# Sheet_1.net
KiCad netlist of a schematic drawn in EasyEDA
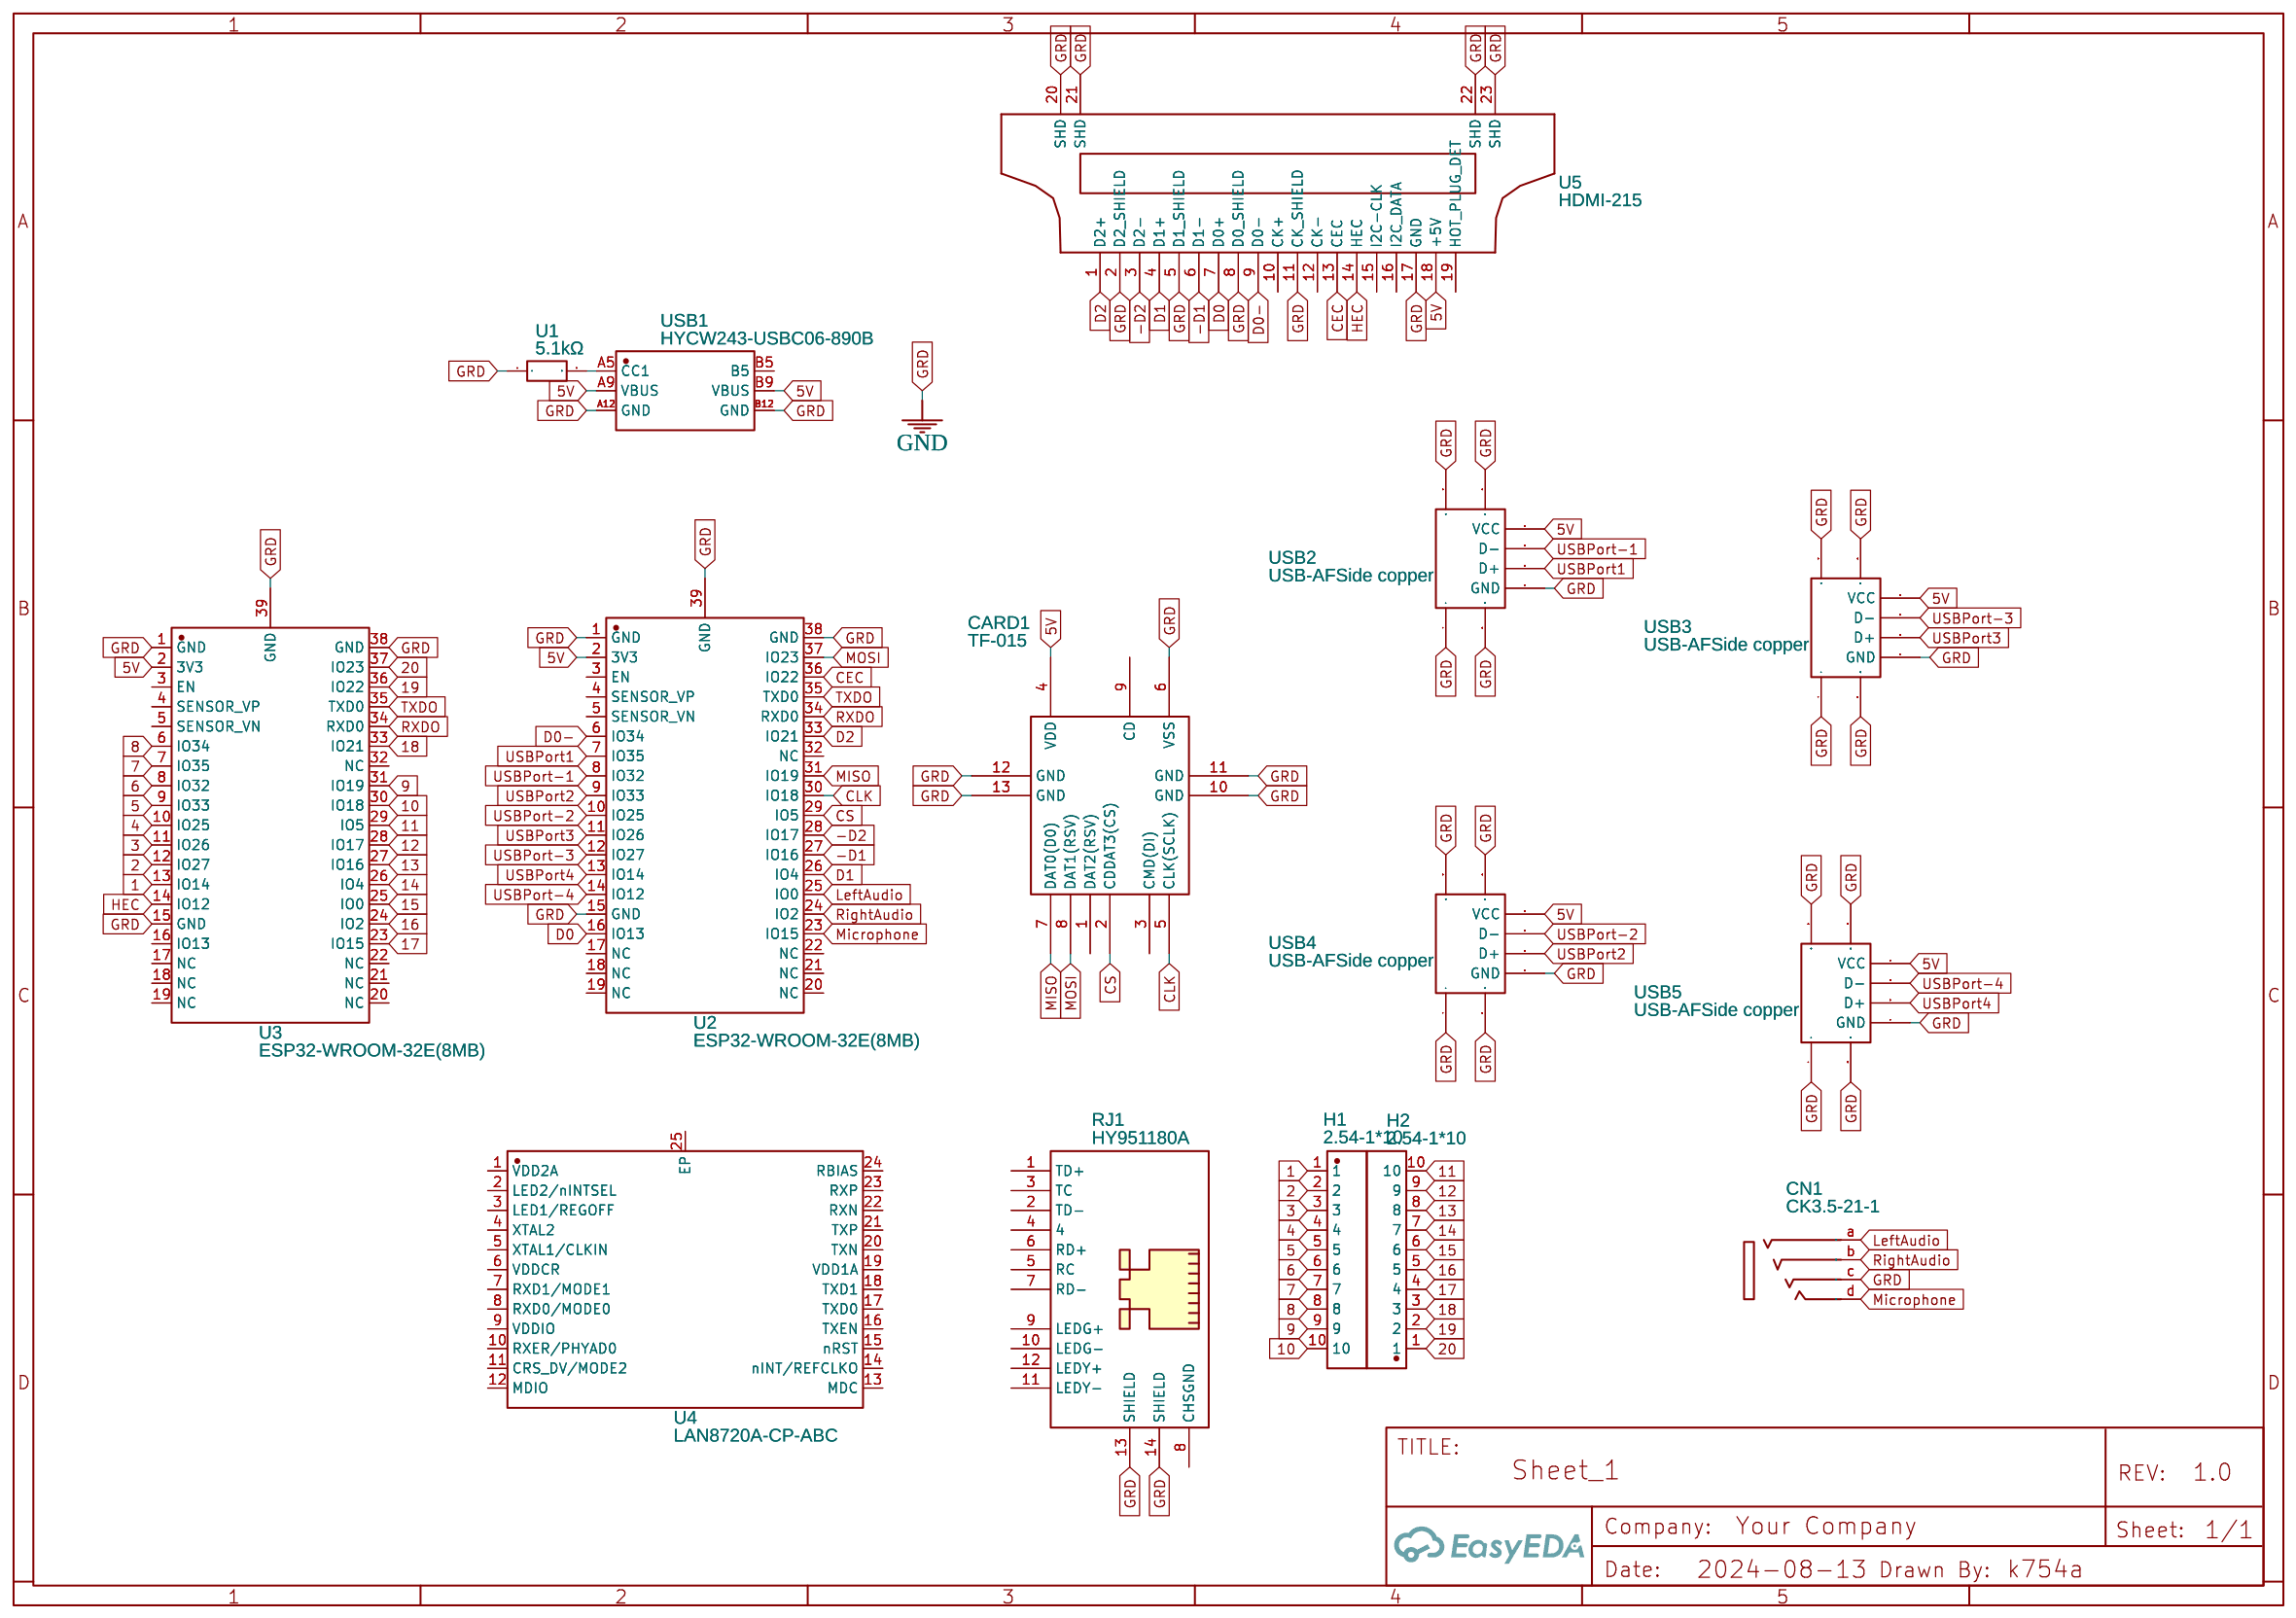
[diagram p0: schematic sheet]

(export (version "E")
  (design (tool "Eeschema 10.0.6"))
  (components
    (comp (ref "CARD1")
      (value "TF-015")
      (fields (field (name "Manufacturer") "SOFNG(硕方)"))
      (libsource (lib "") (part "TF-015"))
    )
    (comp (ref "CN1")
      (value "CK3.5-21-1")
      (fields (field (name "Manufacturer") "JINJIA(金佳)"))
      (libsource (lib "") (part "CK3.5-21-1"))
    )
    (comp (ref "H1")
      (value "2.54-1*10")
      (fields (field (name "Manufacturer") "ZHOURI(洲日)"))
      (libsource (lib "") (part "2.54-1*10_1"))
    )
    (comp (ref "H2")
      (value "2.54-1*10")
      (fields (field (name "Manufacturer") "ZHOURI(洲日)"))
      (libsource (lib "") (part "2.54-1*10"))
    )
    (comp (ref "RJ1")
      (value "HY951180A")
      (fields (field (name "Manufacturer") "HANRUN(汉仁)"))
      (libsource (lib "") (part "HY951180A"))
    )
    (comp (ref "U1")
      (value "5.1kΩ")
      (fields (field (name "Manufacturer Part") "CR1/8W-5K1±5%-ST52") (field (name "Manufacturer") "VO(翔胜)"))
      (libsource (lib "") (part "CR1/8W-5K1±5%-ST52"))
    )
    (comp (ref "U2")
      (value "ESP32-WROOM-32E(8MB)")
      (fields
        (field (name "Manufacturer Part") "ESP32-WROOM-32E-N8")
        (field (name "Manufacturer") "ESPRESSIF(乐鑫)")
      )
      (libsource (lib "") (part "ESP32-WROOM-32E(8MB)"))
    )
    (comp (ref "U3")
      (value "ESP32-WROOM-32E(8MB)")
      (fields
        (field (name "Manufacturer Part") "ESP32-WROOM-32E-N8")
        (field (name "Manufacturer") "ESPRESSIF(乐鑫)")
      )
      (libsource (lib "") (part "ESP32-WROOM-32E(8MB)"))
    )
    (comp (ref "U4")
      (value "LAN8720A-CP-ABC")
      (fields (field (name "Manufacturer") "MICROCHIP(美国微芯)"))
      (libsource (lib "") (part "LAN8720A-CP-ABC"))
    )
    (comp (ref "U5")
      (value "HDMI-215")
      (fields (field (name "Manufacturer") "HANBO(汉博)"))
      (libsource (lib "") (part "HDMI-215"))
    )
    (comp (ref "USB1")
      (value "HYCW243-USBC06-890B")
      (fields (field (name "Manufacturer") "华宇创"))
      (libsource (lib "") (part "HYCW243-USBC06-890B"))
    )
    (comp (ref "USB2")
      (value "USB-AFSide copper")
      (fields (field (name "Manufacturer Part") "USB-AF侧插铜") (field (name "Manufacturer") "精拓金"))
      (libsource (lib "") (part "USB-AFSide copper"))
    )
    (comp (ref "USB3")
      (value "USB-AFSide copper")
      (fields (field (name "Manufacturer Part") "USB-AF侧插铜") (field (name "Manufacturer") "精拓金"))
      (libsource (lib "") (part "USB-AFSide copper"))
    )
    (comp (ref "USB4")
      (value "USB-AFSide copper")
      (fields (field (name "Manufacturer Part") "USB-AF侧插铜") (field (name "Manufacturer") "精拓金"))
      (libsource (lib "") (part "USB-AFSide copper"))
    )
    (comp (ref "USB5")
      (value "USB-AFSide copper")
      (fields (field (name "Manufacturer Part") "USB-AF侧插铜") (field (name "Manufacturer") "精拓金"))
      (libsource (lib "") (part "USB-AFSide copper"))
    )
  )
  (nets
    (net (code "1") (name "-D1") (class "Default")
      (node (ref "U2") (pin "27") (pinfunction "IO16_27") (pintype "unspecified"))
      (node (ref "U5") (pin "6") (pinfunction "D1-_6") (pintype "unspecified"))
    )
    (net (code "2") (name "-D2") (class "Default")
      (node (ref "U2") (pin "28") (pinfunction "IO17_28") (pintype "unspecified"))
      (node (ref "U5") (pin "3") (pinfunction "D2-_3") (pintype "unspecified"))
    )
    (net (code "3") (name "1") (class "Default")
      (node (ref "H1") (pin "1") (pinfunction "1_1") (pintype "unspecified"))
      (node (ref "U3") (pin "13") (pinfunction "IO14_13") (pintype "unspecified"))
    )
    (net (code "4") (name "2") (class "Default")
      (node (ref "H1") (pin "2") (pinfunction "2_2") (pintype "unspecified"))
      (node (ref "U3") (pin "12") (pinfunction "IO27_12") (pintype "unspecified"))
    )
    (net (code "5") (name "3") (class "Default")
      (node (ref "H1") (pin "3") (pinfunction "3_3") (pintype "unspecified"))
      (node (ref "U3") (pin "11") (pinfunction "IO26_11") (pintype "unspecified"))
    )
    (net (code "6") (name "4") (class "Default")
      (node (ref "H1") (pin "4") (pinfunction "4_4") (pintype "unspecified"))
      (node (ref "U3") (pin "10") (pinfunction "IO25_10") (pintype "unspecified"))
    )
    (net (code "7") (name "5") (class "Default")
      (node (ref "H1") (pin "5") (pinfunction "5_5") (pintype "unspecified"))
      (node (ref "U3") (pin "9") (pinfunction "IO33_9") (pintype "unspecified"))
    )
    (net (code "8") (name "5V") (class "Default")
      (node (ref "CARD1") (pin "4") (pinfunction "VDD_4") (pintype "input"))
      (node (ref "U2") (pin "2") (pinfunction "3V3_2") (pintype "unspecified"))
      (node (ref "U3") (pin "2") (pinfunction "3V3_2") (pintype "unspecified"))
      (node (ref "U5") (pin "18") (pinfunction "+5V_18") (pintype "unspecified"))
      (node (ref "USB1") (pin "A9") (pinfunction "VBUS_A9") (pintype "unspecified"))
      (node (ref "USB1") (pin "B9") (pinfunction "VBUS_B9") (pintype "unspecified"))
      (node (ref "USB2") (pin "1") (pinfunction "VCC_1") (pintype "input"))
      (node (ref "USB3") (pin "1") (pinfunction "VCC_1") (pintype "input"))
      (node (ref "USB4") (pin "1") (pinfunction "VCC_1") (pintype "input"))
      (node (ref "USB5") (pin "1") (pinfunction "VCC_1") (pintype "input"))
    )
    (net (code "9") (name "6") (class "Default")
      (node (ref "H1") (pin "6") (pinfunction "6_6") (pintype "unspecified"))
      (node (ref "U3") (pin "8") (pinfunction "IO32_8") (pintype "unspecified"))
    )
    (net (code "10") (name "7") (class "Default")
      (node (ref "H1") (pin "7") (pinfunction "7_7") (pintype "unspecified"))
      (node (ref "U3") (pin "7") (pinfunction "IO35_7") (pintype "unspecified"))
    )
    (net (code "11") (name "8") (class "Default")
      (node (ref "H1") (pin "8") (pinfunction "8_8") (pintype "unspecified"))
      (node (ref "U3") (pin "6") (pinfunction "IO34_6") (pintype "unspecified"))
    )
    (net (code "12") (name "9") (class "Default")
      (node (ref "H1") (pin "9") (pinfunction "9_9") (pintype "unspecified"))
      (node (ref "U3") (pin "31") (pinfunction "IO19_31") (pintype "unspecified"))
    )
    (net (code "13") (name "10") (class "Default")
      (node (ref "H1") (pin "10") (pinfunction "10_10") (pintype "unspecified"))
      (node (ref "U3") (pin "30") (pinfunction "IO18_30") (pintype "unspecified"))
    )
    (net (code "14") (name "11") (class "Default")
      (node (ref "H2") (pin "10") (pinfunction "10_10") (pintype "unspecified"))
      (node (ref "U3") (pin "29") (pinfunction "IO5_29") (pintype "unspecified"))
    )
    (net (code "15") (name "12") (class "Default")
      (node (ref "H2") (pin "9") (pinfunction "9_9") (pintype "unspecified"))
      (node (ref "U3") (pin "28") (pinfunction "IO17_28") (pintype "unspecified"))
    )
    (net (code "16") (name "13") (class "Default")
      (node (ref "H2") (pin "8") (pinfunction "8_8") (pintype "unspecified"))
      (node (ref "U3") (pin "27") (pinfunction "IO16_27") (pintype "unspecified"))
    )
    (net (code "17") (name "14") (class "Default")
      (node (ref "H2") (pin "7") (pinfunction "7_7") (pintype "unspecified"))
      (node (ref "U3") (pin "26") (pinfunction "IO4_26") (pintype "unspecified"))
    )
    (net (code "18") (name "15") (class "Default")
      (node (ref "H2") (pin "6") (pinfunction "6_6") (pintype "unspecified"))
      (node (ref "U3") (pin "25") (pinfunction "IO0_25") (pintype "unspecified"))
    )
    (net (code "19") (name "16") (class "Default")
      (node (ref "H2") (pin "5") (pinfunction "5_5") (pintype "unspecified"))
      (node (ref "U3") (pin "24") (pinfunction "IO2_24") (pintype "unspecified"))
    )
    (net (code "20") (name "17") (class "Default")
      (node (ref "H2") (pin "4") (pinfunction "4_4") (pintype "unspecified"))
      (node (ref "U3") (pin "23") (pinfunction "IO15_23") (pintype "unspecified"))
    )
    (net (code "21") (name "18") (class "Default")
      (node (ref "H2") (pin "3") (pinfunction "3_3") (pintype "unspecified"))
      (node (ref "U3") (pin "33") (pinfunction "IO21_33") (pintype "unspecified"))
    )
    (net (code "22") (name "19") (class "Default")
      (node (ref "H2") (pin "2") (pinfunction "2_2") (pintype "unspecified"))
      (node (ref "U3") (pin "36") (pinfunction "IO22_36") (pintype "unspecified"))
    )
    (net (code "23") (name "20") (class "Default")
      (node (ref "H2") (pin "1") (pinfunction "1_1") (pintype "unspecified"))
      (node (ref "U3") (pin "37") (pinfunction "IO23_37") (pintype "unspecified"))
    )
    (net (code "24") (name "CEC") (class "Default")
      (node (ref "U2") (pin "36") (pinfunction "IO22_36") (pintype "unspecified"))
      (node (ref "U5") (pin "13") (pinfunction "CEC_13") (pintype "unspecified"))
    )
    (net (code "25") (name "CLK") (class "Default")
      (node (ref "CARD1") (pin "5") (pinfunction "CLK(SCLK)_5") (pintype "input"))
      (node (ref "U2") (pin "30") (pinfunction "IO18_30") (pintype "unspecified"))
    )
    (net (code "26") (name "CS") (class "Default")
      (node (ref "CARD1") (pin "2") (pinfunction "CDDAT3(CS)_2") (pintype "bidirectional"))
      (node (ref "U2") (pin "29") (pinfunction "IO5_29") (pintype "unspecified"))
    )
    (net (code "27") (name "D0") (class "Default")
      (node (ref "U2") (pin "16") (pinfunction "IO13_16") (pintype "unspecified"))
      (node (ref "U5") (pin "7") (pinfunction "D0+_7") (pintype "unspecified"))
    )
    (net (code "28") (name "D0-") (class "Default")
      (node (ref "U2") (pin "6") (pinfunction "IO34_6") (pintype "unspecified"))
      (node (ref "U5") (pin "9") (pinfunction "D0-_9") (pintype "unspecified"))
    )
    (net (code "29") (name "D1") (class "Default")
      (node (ref "U2") (pin "26") (pinfunction "IO4_26") (pintype "unspecified"))
      (node (ref "U5") (pin "4") (pinfunction "D1+_4") (pintype "unspecified"))
    )
    (net (code "30") (name "D2") (class "Default")
      (node (ref "U2") (pin "33") (pinfunction "IO21_33") (pintype "unspecified"))
      (node (ref "U5") (pin "1") (pinfunction "D2+_1") (pintype "unspecified"))
    )
    (net (code "31") (name "GRD") (class "Default")
      (node (ref "CARD1") (pin "10") (pinfunction "GND_10") (pintype "input"))
      (node (ref "CARD1") (pin "11") (pinfunction "GND_11") (pintype "input"))
      (node (ref "CARD1") (pin "12") (pinfunction "GND_12") (pintype "input"))
      (node (ref "CARD1") (pin "13") (pinfunction "GND_13") (pintype "input"))
      (node (ref "CARD1") (pin "6") (pinfunction "VSS_6") (pintype "input"))
      (node (ref "CN1") (pin "c") (pinfunction "c_c") (pintype "unspecified"))
      (node (ref "RJ1") (pin "13") (pinfunction "SHIELD_13") (pintype "input"))
      (node (ref "RJ1") (pin "14") (pinfunction "SHIELD_14") (pintype "input"))
      (node (ref "U1") (pin "1") (pinfunction "1_1") (pintype "unspecified"))
      (node (ref "U2") (pin "1") (pinfunction "GND_1") (pintype "unspecified"))
      (node (ref "U2") (pin "15") (pinfunction "GND_15") (pintype "unspecified"))
      (node (ref "U2") (pin "38") (pinfunction "GND_38") (pintype "unspecified"))
      (node (ref "U2") (pin "39") (pinfunction "GND_39") (pintype "unspecified"))
      (node (ref "U3") (pin "1") (pinfunction "GND_1") (pintype "unspecified"))
      (node (ref "U3") (pin "15") (pinfunction "GND_15") (pintype "unspecified"))
      (node (ref "U3") (pin "38") (pinfunction "GND_38") (pintype "unspecified"))
      (node (ref "U3") (pin "39") (pinfunction "GND_39") (pintype "unspecified"))
      (node (ref "U5") (pin "11") (pinfunction "CK_SHIELD_11") (pintype "unspecified"))
      (node (ref "U5") (pin "17") (pinfunction "GND_17") (pintype "unspecified"))
      (node (ref "U5") (pin "2") (pinfunction "D2_SHIELD_2") (pintype "unspecified"))
      (node (ref "U5") (pin "20") (pinfunction "SHD_20") (pintype "unspecified"))
      (node (ref "U5") (pin "21") (pinfunction "SHD_21") (pintype "unspecified"))
      (node (ref "U5") (pin "22") (pinfunction "SHD_22") (pintype "unspecified"))
      (node (ref "U5") (pin "23") (pinfunction "SHD_23") (pintype "unspecified"))
      (node (ref "U5") (pin "5") (pinfunction "D1_SHIELD_5") (pintype "unspecified"))
      (node (ref "U5") (pin "8") (pinfunction "D0_SHIELD_8") (pintype "unspecified"))
      (node (ref "USB1") (pin "A12") (pinfunction "GND_A12") (pintype "unspecified"))
      (node (ref "USB1") (pin "B12") (pinfunction "GND_B12") (pintype "unspecified"))
      (node (ref "USB2") (pin "4") (pinfunction "GND_4") (pintype "input"))
      (node (ref "USB2") (pin "5") (pinfunction "5_5") (pintype "unspecified"))
      (node (ref "USB2") (pin "6") (pinfunction "6_6") (pintype "unspecified"))
      (node (ref "USB2") (pin "7") (pinfunction "7_7") (pintype "unspecified"))
      (node (ref "USB2") (pin "8") (pinfunction "8_8") (pintype "unspecified"))
      (node (ref "USB3") (pin "4") (pinfunction "GND_4") (pintype "input"))
      (node (ref "USB3") (pin "5") (pinfunction "5_5") (pintype "unspecified"))
      (node (ref "USB3") (pin "6") (pinfunction "6_6") (pintype "unspecified"))
      (node (ref "USB3") (pin "7") (pinfunction "7_7") (pintype "unspecified"))
      (node (ref "USB3") (pin "8") (pinfunction "8_8") (pintype "unspecified"))
      (node (ref "USB4") (pin "4") (pinfunction "GND_4") (pintype "input"))
      (node (ref "USB4") (pin "5") (pinfunction "5_5") (pintype "unspecified"))
      (node (ref "USB4") (pin "6") (pinfunction "6_6") (pintype "unspecified"))
      (node (ref "USB4") (pin "7") (pinfunction "7_7") (pintype "unspecified"))
      (node (ref "USB4") (pin "8") (pinfunction "8_8") (pintype "unspecified"))
      (node (ref "USB5") (pin "4") (pinfunction "GND_4") (pintype "input"))
      (node (ref "USB5") (pin "5") (pinfunction "5_5") (pintype "unspecified"))
      (node (ref "USB5") (pin "6") (pinfunction "6_6") (pintype "unspecified"))
      (node (ref "USB5") (pin "7") (pinfunction "7_7") (pintype "unspecified"))
      (node (ref "USB5") (pin "8") (pinfunction "8_8") (pintype "unspecified"))
    )
    (net (code "32") (name "HEC") (class "Default")
      (node (ref "U3") (pin "14") (pinfunction "IO12_14") (pintype "unspecified"))
      (node (ref "U5") (pin "14") (pinfunction "HEC_14") (pintype "unspecified"))
    )
    (net (code "33") (name "LeftAudio") (class "Default")
      (node (ref "CN1") (pin "a") (pinfunction "a_a") (pintype "unspecified"))
      (node (ref "U2") (pin "25") (pinfunction "IO0_25") (pintype "unspecified"))
    )
    (net (code "34") (name "MISO") (class "Default")
      (node (ref "CARD1") (pin "7") (pinfunction "DAT0(D0)_7") (pintype "bidirectional"))
      (node (ref "U2") (pin "31") (pinfunction "IO19_31") (pintype "unspecified"))
    )
    (net (code "35") (name "MOSI") (class "Default")
      (node (ref "CARD1") (pin "8") (pinfunction "DAT1(RSV)_8") (pintype "bidirectional"))
      (node (ref "U2") (pin "37") (pinfunction "IO23_37") (pintype "unspecified"))
    )
    (net (code "36") (name "Microphone") (class "Default")
      (node (ref "CN1") (pin "d") (pinfunction "d_d") (pintype "unspecified"))
      (node (ref "U2") (pin "23") (pinfunction "IO15_23") (pintype "unspecified"))
    )
    (net (code "37") (name "Net-(USB1-CC1)") (class "Default")
      (node (ref "U1") (pin "2") (pinfunction "2_2") (pintype "unspecified"))
      (node (ref "USB1") (pin "A5") (pinfunction "CC1_A5") (pintype "unspecified"))
    )
    (net (code "38") (name "RXDO") (class "Default")
      (node (ref "U2") (pin "34") (pinfunction "RXD0_34") (pintype "unspecified"))
      (node (ref "U3") (pin "34") (pinfunction "RXD0_34") (pintype "unspecified"))
    )
    (net (code "39") (name "RightAudio") (class "Default")
      (node (ref "CN1") (pin "b") (pinfunction "b_b") (pintype "unspecified"))
      (node (ref "U2") (pin "24") (pinfunction "IO2_24") (pintype "unspecified"))
    )
    (net (code "40") (name "TXDO") (class "Default")
      (node (ref "U2") (pin "35") (pinfunction "TXD0_35") (pintype "unspecified"))
      (node (ref "U3") (pin "35") (pinfunction "TXD0_35") (pintype "unspecified"))
    )
    (net (code "41") (name "USBPort-1") (class "Default")
      (node (ref "U2") (pin "8") (pinfunction "IO32_8") (pintype "unspecified"))
      (node (ref "USB2") (pin "2") (pinfunction "D-_2") (pintype "input"))
    )
    (net (code "42") (name "USBPort-2") (class "Default")
      (node (ref "U2") (pin "10") (pinfunction "IO25_10") (pintype "unspecified"))
      (node (ref "USB4") (pin "2") (pinfunction "D-_2") (pintype "input"))
    )
    (net (code "43") (name "USBPort-3") (class "Default")
      (node (ref "U2") (pin "12") (pinfunction "IO27_12") (pintype "unspecified"))
      (node (ref "USB3") (pin "2") (pinfunction "D-_2") (pintype "input"))
    )
    (net (code "44") (name "USBPort-4") (class "Default")
      (node (ref "U2") (pin "14") (pinfunction "IO12_14") (pintype "unspecified"))
      (node (ref "USB5") (pin "2") (pinfunction "D-_2") (pintype "input"))
    )
    (net (code "45") (name "USBPort1") (class "Default")
      (node (ref "U2") (pin "7") (pinfunction "IO35_7") (pintype "unspecified"))
      (node (ref "USB2") (pin "3") (pinfunction "D+_3") (pintype "input"))
    )
    (net (code "46") (name "USBPort2") (class "Default")
      (node (ref "U2") (pin "9") (pinfunction "IO33_9") (pintype "unspecified"))
      (node (ref "USB4") (pin "3") (pinfunction "D+_3") (pintype "input"))
    )
    (net (code "47") (name "USBPort3") (class "Default")
      (node (ref "U2") (pin "11") (pinfunction "IO26_11") (pintype "unspecified"))
      (node (ref "USB3") (pin "3") (pinfunction "D+_3") (pintype "input"))
    )
    (net (code "48") (name "USBPort4") (class "Default")
      (node (ref "U2") (pin "13") (pinfunction "IO14_13") (pintype "unspecified"))
      (node (ref "USB5") (pin "3") (pinfunction "D+_3") (pintype "input"))
    )
    (net (code "49") (name "unconnected-(CARD1-CD-Pad9)") (class "Default")
      (node (ref "CARD1") (pin "9") (pinfunction "CD_9") (pintype "input"))
    )
    (net (code "50") (name "unconnected-(CARD1-CMD(DI)-Pad3)") (class "Default")
      (node (ref "CARD1") (pin "3") (pinfunction "CMD(DI)_3") (pintype "input"))
    )
    (net (code "51") (name "unconnected-(CARD1-DAT2(RSV)-Pad1)") (class "Default")
      (node (ref "CARD1") (pin "1") (pinfunction "DAT2(RSV)_1") (pintype "bidirectional"))
    )
    (net (code "52") (name "unconnected-(RJ1-CHSGND-Pad8)") (class "Default")
      (node (ref "RJ1") (pin "8") (pinfunction "CHSGND_8") (pintype "input"))
    )
    (net (code "53") (name "unconnected-(RJ1-LEDG+-Pad9)") (class "Default")
      (node (ref "RJ1") (pin "9") (pinfunction "LEDG+_9") (pintype "input"))
    )
    (net (code "54") (name "unconnected-(RJ1-LEDG--Pad10)") (class "Default")
      (node (ref "RJ1") (pin "10") (pinfunction "LEDG-_10") (pintype "input"))
    )
    (net (code "55") (name "unconnected-(RJ1-LEDY+-Pad12)") (class "Default")
      (node (ref "RJ1") (pin "12") (pinfunction "LEDY+_12") (pintype "input"))
    )
    (net (code "56") (name "unconnected-(RJ1-LEDY--Pad11)") (class "Default")
      (node (ref "RJ1") (pin "11") (pinfunction "LEDY-_11") (pintype "input"))
    )
    (net (code "57") (name "unconnected-(RJ1-Pad4)") (class "Default")
      (node (ref "RJ1") (pin "4") (pinfunction "4_4") (pintype "unspecified"))
    )
    (net (code "58") (name "unconnected-(RJ1-RC-Pad5)") (class "Default")
      (node (ref "RJ1") (pin "5") (pinfunction "RC_5") (pintype "input"))
    )
    (net (code "59") (name "unconnected-(RJ1-RD+-Pad6)") (class "Default")
      (node (ref "RJ1") (pin "6") (pinfunction "RD+_6") (pintype "input"))
    )
    (net (code "60") (name "unconnected-(RJ1-RD--Pad7)") (class "Default")
      (node (ref "RJ1") (pin "7") (pinfunction "RD-_7") (pintype "input"))
    )
    (net (code "61") (name "unconnected-(RJ1-TC-Pad3)") (class "Default")
      (node (ref "RJ1") (pin "3") (pinfunction "TC_3") (pintype "input"))
    )
    (net (code "62") (name "unconnected-(RJ1-TD+-Pad1)") (class "Default")
      (node (ref "RJ1") (pin "1") (pinfunction "TD+_1") (pintype "input"))
    )
    (net (code "63") (name "unconnected-(RJ1-TD--Pad2)") (class "Default")
      (node (ref "RJ1") (pin "2") (pinfunction "TD-_2") (pintype "input"))
    )
    (net (code "64") (name "unconnected-(U2-EN-Pad3)") (class "Default")
      (node (ref "U2") (pin "3") (pinfunction "EN_3") (pintype "unspecified"))
    )
    (net (code "65") (name "unconnected-(U2-NC-Pad17)") (class "Default")
      (node (ref "U2") (pin "17") (pinfunction "NC_17") (pintype "unspecified"))
    )
    (net (code "66") (name "unconnected-(U2-NC-Pad18)") (class "Default")
      (node (ref "U2") (pin "18") (pinfunction "NC_18") (pintype "unspecified"))
    )
    (net (code "67") (name "unconnected-(U2-NC-Pad19)") (class "Default")
      (node (ref "U2") (pin "19") (pinfunction "NC_19") (pintype "unspecified"))
    )
    (net (code "68") (name "unconnected-(U2-NC-Pad20)") (class "Default")
      (node (ref "U2") (pin "20") (pinfunction "NC_20") (pintype "unspecified"))
    )
    (net (code "69") (name "unconnected-(U2-NC-Pad21)") (class "Default")
      (node (ref "U2") (pin "21") (pinfunction "NC_21") (pintype "unspecified"))
    )
    (net (code "70") (name "unconnected-(U2-NC-Pad22)") (class "Default")
      (node (ref "U2") (pin "22") (pinfunction "NC_22") (pintype "unspecified"))
    )
    (net (code "71") (name "unconnected-(U2-NC-Pad32)") (class "Default")
      (node (ref "U2") (pin "32") (pinfunction "NC_32") (pintype "unspecified"))
    )
    (net (code "72") (name "unconnected-(U2-SENSOR_VN-Pad5)") (class "Default")
      (node (ref "U2") (pin "5") (pinfunction "SENSOR_VN_5") (pintype "unspecified"))
    )
    (net (code "73") (name "unconnected-(U2-SENSOR_VP-Pad4)") (class "Default")
      (node (ref "U2") (pin "4") (pinfunction "SENSOR_VP_4") (pintype "unspecified"))
    )
    (net (code "74") (name "unconnected-(U3-EN-Pad3)") (class "Default")
      (node (ref "U3") (pin "3") (pinfunction "EN_3") (pintype "unspecified"))
    )
    (net (code "75") (name "unconnected-(U3-IO13-Pad16)") (class "Default")
      (node (ref "U3") (pin "16") (pinfunction "IO13_16") (pintype "unspecified"))
    )
    (net (code "76") (name "unconnected-(U3-NC-Pad17)") (class "Default")
      (node (ref "U3") (pin "17") (pinfunction "NC_17") (pintype "unspecified"))
    )
    (net (code "77") (name "unconnected-(U3-NC-Pad18)") (class "Default")
      (node (ref "U3") (pin "18") (pinfunction "NC_18") (pintype "unspecified"))
    )
    (net (code "78") (name "unconnected-(U3-NC-Pad19)") (class "Default")
      (node (ref "U3") (pin "19") (pinfunction "NC_19") (pintype "unspecified"))
    )
    (net (code "79") (name "unconnected-(U3-NC-Pad20)") (class "Default")
      (node (ref "U3") (pin "20") (pinfunction "NC_20") (pintype "unspecified"))
    )
    (net (code "80") (name "unconnected-(U3-NC-Pad21)") (class "Default")
      (node (ref "U3") (pin "21") (pinfunction "NC_21") (pintype "unspecified"))
    )
    (net (code "81") (name "unconnected-(U3-NC-Pad22)") (class "Default")
      (node (ref "U3") (pin "22") (pinfunction "NC_22") (pintype "unspecified"))
    )
    (net (code "82") (name "unconnected-(U3-NC-Pad32)") (class "Default")
      (node (ref "U3") (pin "32") (pinfunction "NC_32") (pintype "unspecified"))
    )
    (net (code "83") (name "unconnected-(U3-SENSOR_VN-Pad5)") (class "Default")
      (node (ref "U3") (pin "5") (pinfunction "SENSOR_VN_5") (pintype "unspecified"))
    )
    (net (code "84") (name "unconnected-(U3-SENSOR_VP-Pad4)") (class "Default")
      (node (ref "U3") (pin "4") (pinfunction "SENSOR_VP_4") (pintype "unspecified"))
    )
    (net (code "85") (name "unconnected-(U4-CRS_DV{slash}MODE2-Pad11)") (class "Default")
      (node (ref "U4") (pin "11") (pinfunction "CRS_DV/MODE2_11") (pintype "unspecified"))
    )
    (net (code "86") (name "unconnected-(U4-EP-Pad25)") (class "Default")
      (node (ref "U4") (pin "25") (pinfunction "EP_25") (pintype "unspecified"))
    )
    (net (code "87") (name "unconnected-(U4-LED1{slash}REGOFF-Pad3)") (class "Default")
      (node (ref "U4") (pin "3") (pinfunction "LED1/REGOFF_3") (pintype "unspecified"))
    )
    (net (code "88") (name "unconnected-(U4-LED2{slash}nINTSEL-Pad2)") (class "Default")
      (node (ref "U4") (pin "2") (pinfunction "LED2/nINTSEL_2") (pintype "unspecified"))
    )
    (net (code "89") (name "unconnected-(U4-MDC-Pad13)") (class "Default")
      (node (ref "U4") (pin "13") (pinfunction "MDC_13") (pintype "unspecified"))
    )
    (net (code "90") (name "unconnected-(U4-MDIO-Pad12)") (class "Default")
      (node (ref "U4") (pin "12") (pinfunction "MDIO_12") (pintype "unspecified"))
    )
    (net (code "91") (name "unconnected-(U4-RBIAS-Pad24)") (class "Default")
      (node (ref "U4") (pin "24") (pinfunction "RBIAS_24") (pintype "unspecified"))
    )
    (net (code "92") (name "unconnected-(U4-RXD0{slash}MODE0-Pad8)") (class "Default")
      (node (ref "U4") (pin "8") (pinfunction "RXD0/MODE0_8") (pintype "unspecified"))
    )
    (net (code "93") (name "unconnected-(U4-RXD1{slash}MODE1-Pad7)") (class "Default")
      (node (ref "U4") (pin "7") (pinfunction "RXD1/MODE1_7") (pintype "unspecified"))
    )
    (net (code "94") (name "unconnected-(U4-RXER{slash}PHYAD0-Pad10)") (class "Default")
      (node (ref "U4") (pin "10") (pinfunction "RXER/PHYAD0_10") (pintype "unspecified"))
    )
    (net (code "95") (name "unconnected-(U4-RXN-Pad22)") (class "Default")
      (node (ref "U4") (pin "22") (pinfunction "RXN_22") (pintype "unspecified"))
    )
    (net (code "96") (name "unconnected-(U4-RXP-Pad23)") (class "Default")
      (node (ref "U4") (pin "23") (pinfunction "RXP_23") (pintype "unspecified"))
    )
    (net (code "97") (name "unconnected-(U4-TXD0-Pad17)") (class "Default")
      (node (ref "U4") (pin "17") (pinfunction "TXD0_17") (pintype "unspecified"))
    )
    (net (code "98") (name "unconnected-(U4-TXD1-Pad18)") (class "Default")
      (node (ref "U4") (pin "18") (pinfunction "TXD1_18") (pintype "unspecified"))
    )
    (net (code "99") (name "unconnected-(U4-TXEN-Pad16)") (class "Default")
      (node (ref "U4") (pin "16") (pinfunction "TXEN_16") (pintype "unspecified"))
    )
    (net (code "100") (name "unconnected-(U4-TXN-Pad20)") (class "Default")
      (node (ref "U4") (pin "20") (pinfunction "TXN_20") (pintype "unspecified"))
    )
    (net (code "101") (name "unconnected-(U4-TXP-Pad21)") (class "Default")
      (node (ref "U4") (pin "21") (pinfunction "TXP_21") (pintype "unspecified"))
    )
    (net (code "102") (name "unconnected-(U4-VDD1A-Pad19)") (class "Default")
      (node (ref "U4") (pin "19") (pinfunction "VDD1A_19") (pintype "unspecified"))
    )
    (net (code "103") (name "unconnected-(U4-VDD2A-Pad1)") (class "Default")
      (node (ref "U4") (pin "1") (pinfunction "VDD2A_1") (pintype "unspecified"))
    )
    (net (code "104") (name "unconnected-(U4-VDDCR-Pad6)") (class "Default")
      (node (ref "U4") (pin "6") (pinfunction "VDDCR_6") (pintype "unspecified"))
    )
    (net (code "105") (name "unconnected-(U4-VDDIO-Pad9)") (class "Default")
      (node (ref "U4") (pin "9") (pinfunction "VDDIO_9") (pintype "unspecified"))
    )
    (net (code "106") (name "unconnected-(U4-XTAL1{slash}CLKIN-Pad5)") (class "Default")
      (node (ref "U4") (pin "5") (pinfunction "XTAL1/CLKIN_5") (pintype "unspecified"))
    )
    (net (code "107") (name "unconnected-(U4-XTAL2-Pad4)") (class "Default")
      (node (ref "U4") (pin "4") (pinfunction "XTAL2_4") (pintype "unspecified"))
    )
    (net (code "108") (name "unconnected-(U4-nINT{slash}REFCLKO-Pad14)") (class "Default")
      (node (ref "U4") (pin "14") (pinfunction "nINT/REFCLKO_14") (pintype "unspecified"))
    )
    (net (code "109") (name "unconnected-(U4-nRST-Pad15)") (class "Default")
      (node (ref "U4") (pin "15") (pinfunction "nRST_15") (pintype "unspecified"))
    )
    (net (code "110") (name "unconnected-(U5-CK+-Pad10)") (class "Default")
      (node (ref "U5") (pin "10") (pinfunction "CK+_10") (pintype "unspecified"))
    )
    (net (code "111") (name "unconnected-(U5-CK--Pad12)") (class "Default")
      (node (ref "U5") (pin "12") (pinfunction "CK-_12") (pintype "unspecified"))
    )
    (net (code "112") (name "unconnected-(U5-HOT_PLUG_DET-Pad19)") (class "Default")
      (node (ref "U5") (pin "19") (pinfunction "HOT_PLUG_DET_19") (pintype "unspecified"))
    )
    (net (code "113") (name "unconnected-(U5-I2C-CLK-Pad15)") (class "Default")
      (node (ref "U5") (pin "15") (pinfunction "I2C-CLK_15") (pintype "unspecified"))
    )
    (net (code "114") (name "unconnected-(U5-I2C_DATA-Pad16)") (class "Default")
      (node (ref "U5") (pin "16") (pinfunction "I2C_DATA_16") (pintype "unspecified"))
    )
    (net (code "115") (name "unconnected-(USB1-PadB5)") (class "Default")
      (node (ref "USB1") (pin "B5") (pinfunction "B5_B5") (pintype "unspecified"))
    )
  )
)
